# SCH_RTK2B_Micro_F9P_Breakout_Board_v2_0_.net
KiCad netlist of a schematic drawn in EasyEDA
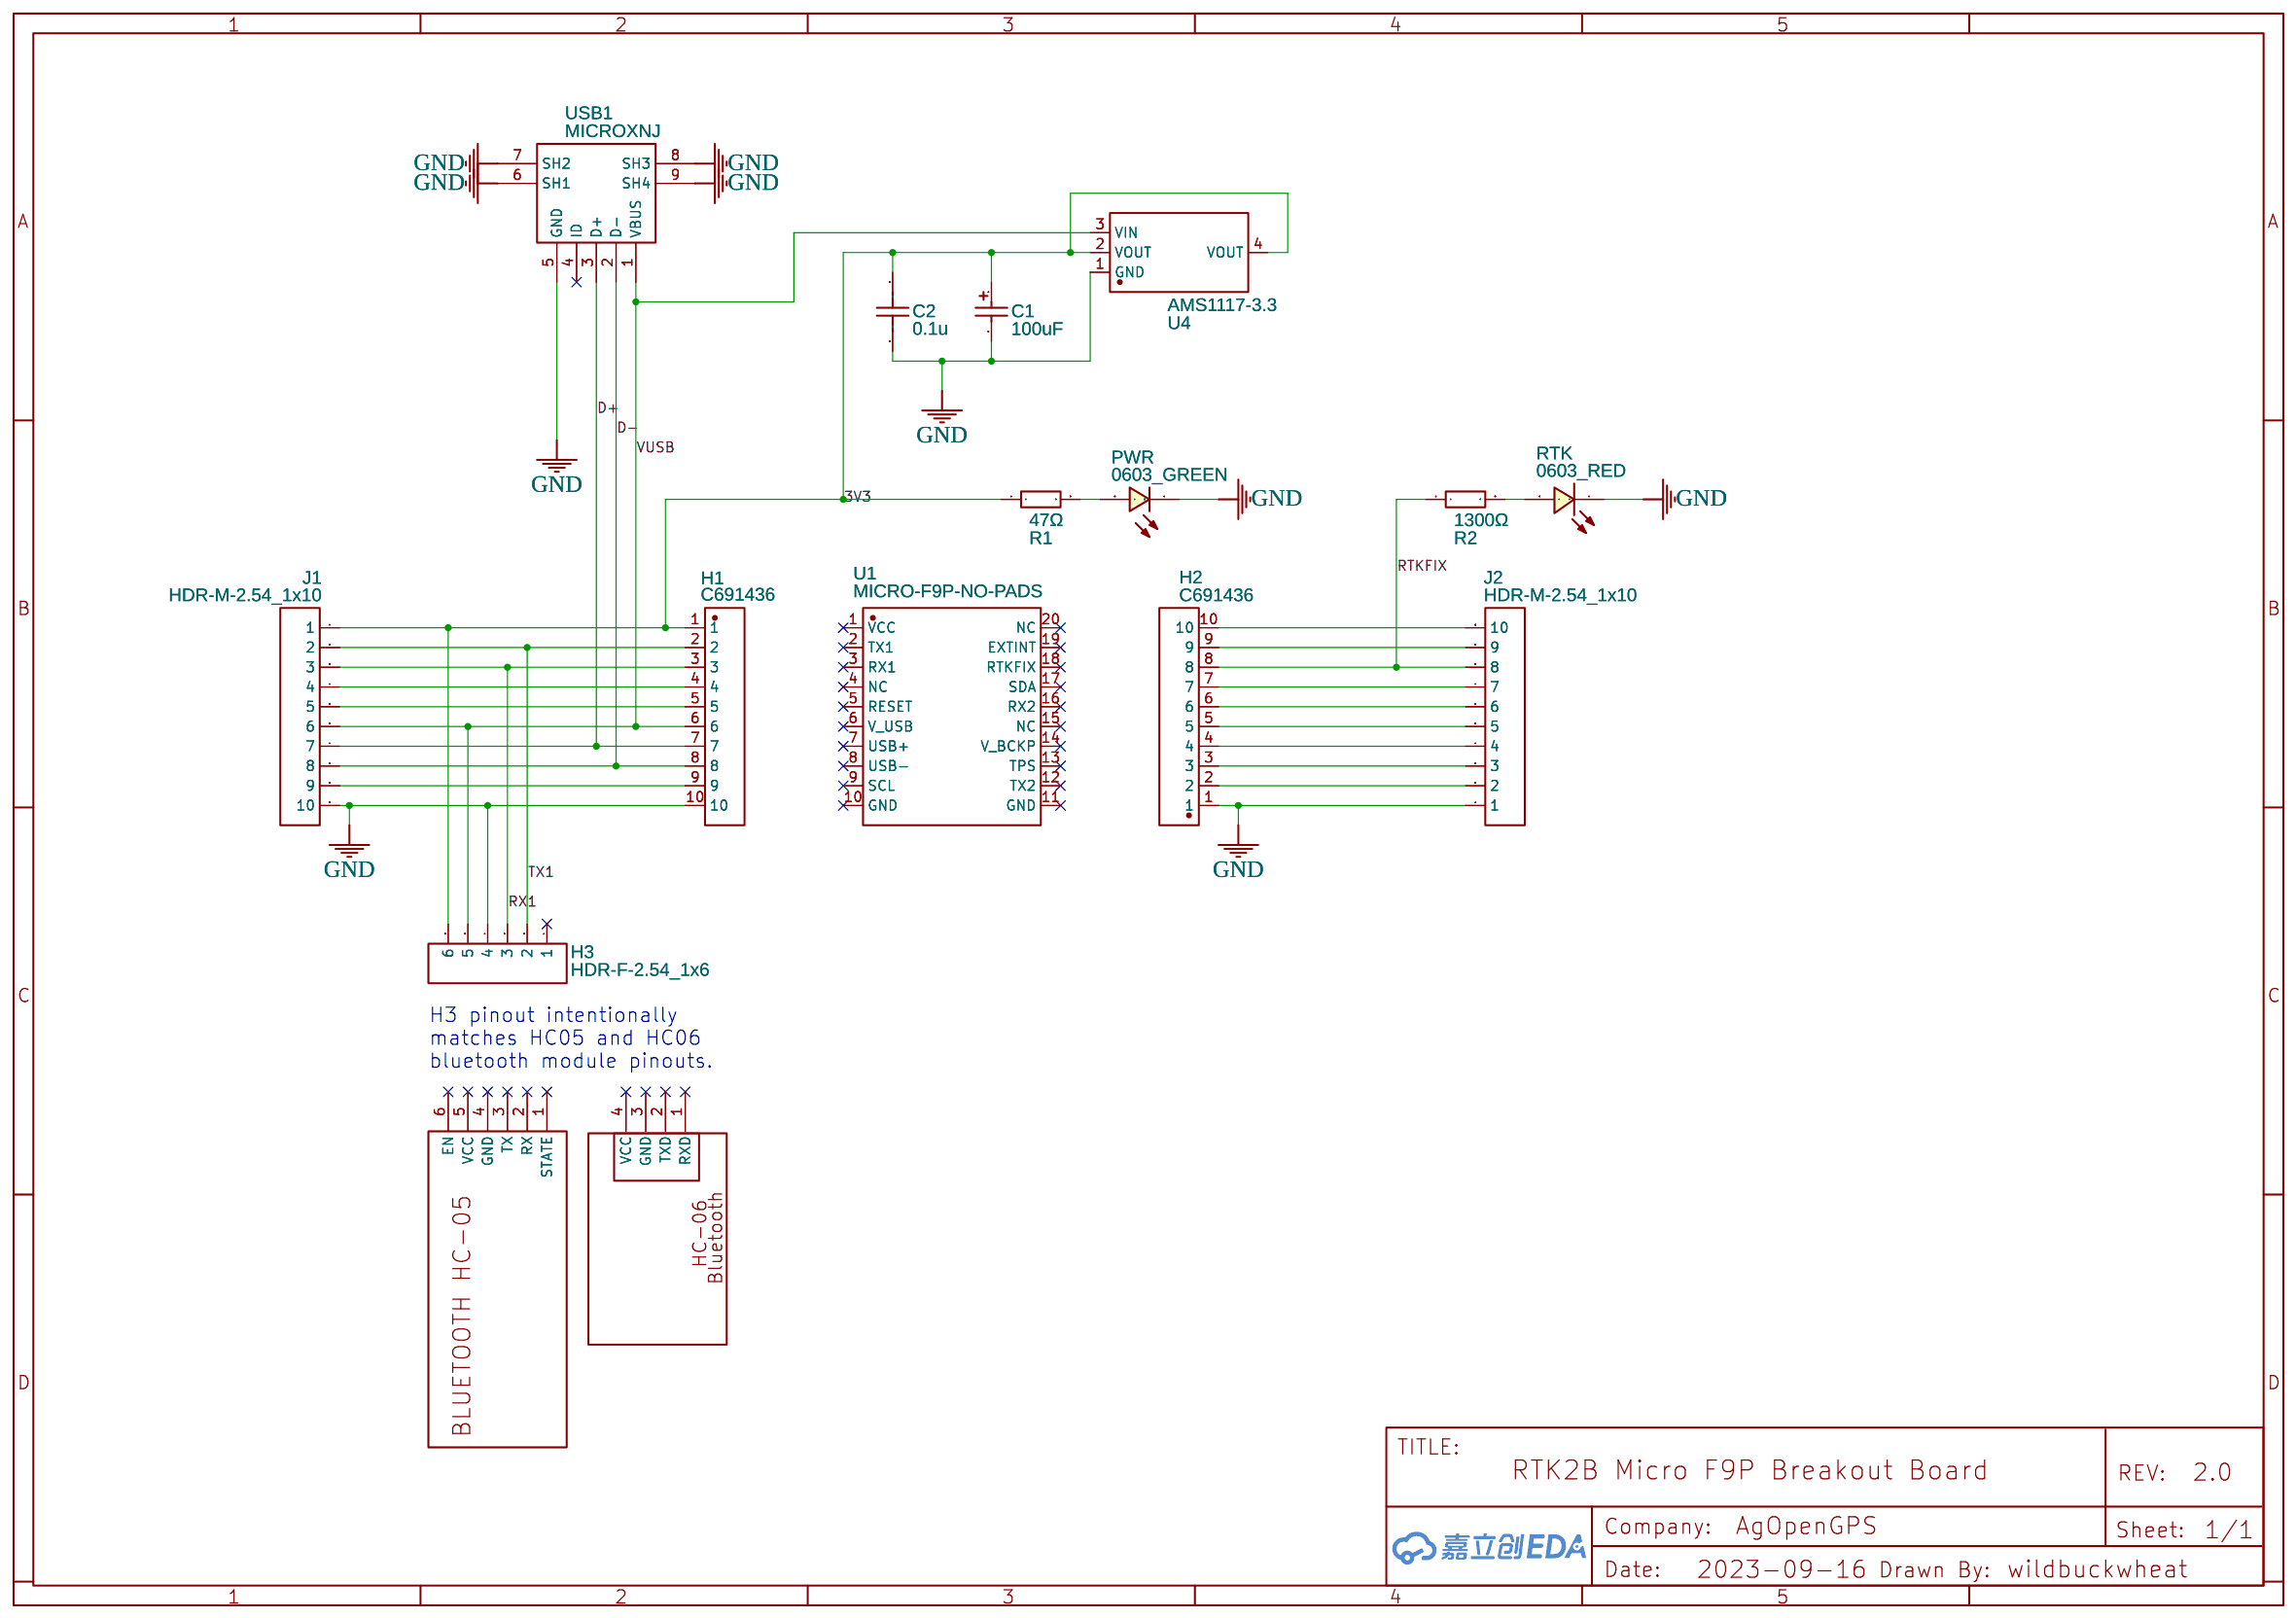
[diagram p0: schematic sheet]

(export (version "E")
  (design (tool "Eeschema 10.0.6"))
  (components
    (comp (ref "C1")
      (value "100uF")
      (fields (field (name "Manufacturer Part") "TAJB107K006RNJ") (field (name "Manufacturer") "Kyocera AVX"))
      (libsource (lib "") (part "TAJB107K006RNJ"))
    )
    (comp (ref "C2") (value "0.1u") (libsource (lib "") (part "C_0603_US")))
    (comp (ref "H1")
      (value "C691436")
      (fields (field (name "Manufacturer") "BOOMELE(Boom Precision Elec)"))
      (libsource (lib "") (part "C691436"))
    )
    (comp (ref "H2")
      (value "C691436")
      (fields (field (name "Manufacturer") "BOOMELE(Boom Precision Elec)"))
      (libsource (lib "") (part "C691436_1"))
    )
    (comp (ref "H3") (value "HDR-F-2.54_1x6") (libsource (lib "") (part "HDR-F-2.54_1x6")))
    (comp (ref "J1") (value "HDR-M-2.54_1x10") (libsource (lib "") (part "HDR-M-2.54_1x10_1")))
    (comp (ref "J2") (value "HDR-M-2.54_1x10") (libsource (lib "") (part "HDR-M-2.54_1x10")))
    (comp (ref "MK1") (value "Modulo_Bluetooth_HC-06") (libsource (lib "") (part "Modulo_Bluetooth_HC-06")))
    (comp (ref "PWR")
      (value "0603_GREEN")
      (fields
        (field (name "Manufacturer Part") "19-217/GHC-YR1S2/3T")
        (field (name "Manufacturer") "EVERLIGHT(亿光)")
      )
      (libsource (lib "") (part "19-217/GHC-YR1S2/3T-GREEN"))
    )
    (comp (ref "R1")
      (value "47Ω")
      (fields
        (field (name "Manufacturer Part") "0603WAF470JT5E")
        (field (name "Manufacturer") "UNI-ROYAL(厚声)")
      )
      (libsource (lib "") (part "0603WAF470JT5E"))
    )
    (comp (ref "R2")
      (value "1300Ω")
      (fields
        (field (name "Manufacturer Part") "0603WAF470JT5E")
        (field (name "Manufacturer") "UNI-ROYAL(厚声)")
      )
      (libsource (lib "") (part "0603WAF470JT5E"))
    )
    (comp (ref "RTK")
      (value "0603_RED")
      (fields (field (name "Manufacturer Part") "KT-0603R"))
      (libsource (lib "") (part "KT-0603R-RED"))
    )
    (comp (ref "U1") (value "MICRO-F9P-NO-PADS") (libsource (lib "") (part "MICRO-F9P-NO-PADS")))
    (comp (ref "U2")
      (value "BLUETOOTH HC05 COPY")
      (fields (field (name "Manufacturer Part") "BLUETOOTH HC05"))
      (libsource (lib "") (part "BLUETOOTH HC05 COPY"))
    )
    (comp (ref "U4")
      (value "AMS1117-3.3")
      (fields (field (name "Manufacturer") "AMS"))
      (libsource (lib "") (part "AMS1117-3.3"))
    )
    (comp (ref "USB1")
      (value "MICROXNJ")
      (fields (field (name "Manufacturer Part") "MicroXNJ") (field (name "Manufacturer") "SHOU HAN(首韩)"))
      (libsource (lib "") (part "MICROXNJ"))
    )
  )
  (nets
    (net (code "1") (name "/3V3") (class "Default")
      (node (ref "C1") (pin "1") (pinfunction "1_1") (pintype "input"))
      (node (ref "C2") (pin "2") (pinfunction "2_2") (pintype "unspecified"))
      (node (ref "H1") (pin "1") (pinfunction "1_1") (pintype "unspecified"))
      (node (ref "H3") (pin "6") (pinfunction "6_6") (pintype "input"))
      (node (ref "J1") (pin "1") (pinfunction "1_1") (pintype "unspecified"))
      (node (ref "R1") (pin "1") (pinfunction "1_1") (pintype "input"))
      (node (ref "U4") (pin "2") (pinfunction "VOUT_2") (pintype "unspecified"))
      (node (ref "U4") (pin "4") (pinfunction "VOUT_4") (pintype "unspecified"))
    )
    (net (code "2") (name "/D+") (class "Default")
      (node (ref "H1") (pin "7") (pinfunction "7_7") (pintype "unspecified"))
      (node (ref "J1") (pin "7") (pinfunction "7_7") (pintype "unspecified"))
      (node (ref "USB1") (pin "3") (pinfunction "D+_3") (pintype "unspecified"))
    )
    (net (code "3") (name "/D-") (class "Default")
      (node (ref "H1") (pin "8") (pinfunction "8_8") (pintype "unspecified"))
      (node (ref "J1") (pin "8") (pinfunction "8_8") (pintype "unspecified"))
      (node (ref "USB1") (pin "2") (pinfunction "D-_2") (pintype "unspecified"))
    )
    (net (code "4") (name "/RTKFIX") (class "Default")
      (node (ref "H2") (pin "8") (pinfunction "8_8") (pintype "unspecified"))
      (node (ref "J2") (pin "8") (pinfunction "8_8") (pintype "unspecified"))
      (node (ref "R2") (pin "1") (pinfunction "1_1") (pintype "input"))
    )
    (net (code "5") (name "/RX1") (class "Default")
      (node (ref "H1") (pin "3") (pinfunction "3_3") (pintype "unspecified"))
      (node (ref "H3") (pin "3") (pinfunction "3_3") (pintype "input"))
      (node (ref "J1") (pin "3") (pinfunction "3_3") (pintype "unspecified"))
    )
    (net (code "6") (name "/TX1") (class "Default")
      (node (ref "H1") (pin "2") (pinfunction "2_2") (pintype "unspecified"))
      (node (ref "H3") (pin "2") (pinfunction "2_2") (pintype "input"))
      (node (ref "J1") (pin "2") (pinfunction "2_2") (pintype "unspecified"))
    )
    (net (code "7") (name "/VUSB") (class "Default")
      (node (ref "H1") (pin "6") (pinfunction "6_6") (pintype "unspecified"))
      (node (ref "H3") (pin "5") (pinfunction "5_5") (pintype "input"))
      (node (ref "J1") (pin "6") (pinfunction "6_6") (pintype "unspecified"))
      (node (ref "U4") (pin "3") (pinfunction "VIN_3") (pintype "unspecified"))
      (node (ref "USB1") (pin "1") (pinfunction "VBUS_1") (pintype "unspecified"))
    )
    (net (code "8") (name "GND") (class "Default")
      (node (ref "C1") (pin "2") (pinfunction "2_2") (pintype "input"))
      (node (ref "C2") (pin "1") (pinfunction "1_1") (pintype "unspecified"))
      (node (ref "H1") (pin "10") (pinfunction "10_10") (pintype "unspecified"))
      (node (ref "H2") (pin "1") (pinfunction "1_1") (pintype "unspecified"))
      (node (ref "H3") (pin "4") (pinfunction "4_4") (pintype "input"))
      (node (ref "J1") (pin "10") (pinfunction "10_10") (pintype "unspecified"))
      (node (ref "J2") (pin "1") (pinfunction "1_1") (pintype "unspecified"))
      (node (ref "PWR") (pin "1") (pinfunction "C_1") (pintype "input"))
      (node (ref "RTK") (pin "1") (pinfunction "K_1") (pintype "unspecified"))
      (node (ref "U4") (pin "1") (pinfunction "GND_1") (pintype "unspecified"))
      (node (ref "USB1") (pin "5") (pinfunction "GND_5") (pintype "unspecified"))
      (node (ref "USB1") (pin "6") (pinfunction "SH1_6") (pintype "unspecified"))
      (node (ref "USB1") (pin "7") (pinfunction "SH2_7") (pintype "unspecified"))
      (node (ref "USB1") (pin "8") (pinfunction "SH3_8") (pintype "unspecified"))
      (node (ref "USB1") (pin "9") (pinfunction "SH4_9") (pintype "unspecified"))
    )
    (net (code "9") (name "Net-(H1-Pad4)") (class "Default")
      (node (ref "H1") (pin "4") (pinfunction "4_4") (pintype "unspecified"))
      (node (ref "J1") (pin "4") (pinfunction "4_4") (pintype "unspecified"))
    )
    (net (code "10") (name "Net-(H1-Pad5)") (class "Default")
      (node (ref "H1") (pin "5") (pinfunction "5_5") (pintype "unspecified"))
      (node (ref "J1") (pin "5") (pinfunction "5_5") (pintype "unspecified"))
    )
    (net (code "11") (name "Net-(H1-Pad9)") (class "Default")
      (node (ref "H1") (pin "9") (pinfunction "9_9") (pintype "unspecified"))
      (node (ref "J1") (pin "9") (pinfunction "9_9") (pintype "unspecified"))
    )
    (net (code "12") (name "Net-(H2-Pad2)") (class "Default")
      (node (ref "H2") (pin "2") (pinfunction "2_2") (pintype "unspecified"))
      (node (ref "J2") (pin "2") (pinfunction "2_2") (pintype "unspecified"))
    )
    (net (code "13") (name "Net-(H2-Pad3)") (class "Default")
      (node (ref "H2") (pin "3") (pinfunction "3_3") (pintype "unspecified"))
      (node (ref "J2") (pin "3") (pinfunction "3_3") (pintype "unspecified"))
    )
    (net (code "14") (name "Net-(H2-Pad4)") (class "Default")
      (node (ref "H2") (pin "4") (pinfunction "4_4") (pintype "unspecified"))
      (node (ref "J2") (pin "4") (pinfunction "4_4") (pintype "unspecified"))
    )
    (net (code "15") (name "Net-(H2-Pad5)") (class "Default")
      (node (ref "H2") (pin "5") (pinfunction "5_5") (pintype "unspecified"))
      (node (ref "J2") (pin "5") (pinfunction "5_5") (pintype "unspecified"))
    )
    (net (code "16") (name "Net-(H2-Pad6)") (class "Default")
      (node (ref "H2") (pin "6") (pinfunction "6_6") (pintype "unspecified"))
      (node (ref "J2") (pin "6") (pinfunction "6_6") (pintype "unspecified"))
    )
    (net (code "17") (name "Net-(H2-Pad7)") (class "Default")
      (node (ref "H2") (pin "7") (pinfunction "7_7") (pintype "unspecified"))
      (node (ref "J2") (pin "7") (pinfunction "7_7") (pintype "unspecified"))
    )
    (net (code "18") (name "Net-(H2-Pad9)") (class "Default")
      (node (ref "H2") (pin "9") (pinfunction "9_9") (pintype "unspecified"))
      (node (ref "J2") (pin "9") (pinfunction "9_9") (pintype "unspecified"))
    )
    (net (code "19") (name "Net-(H2-Pad10)") (class "Default")
      (node (ref "H2") (pin "10") (pinfunction "10_10") (pintype "unspecified"))
      (node (ref "J2") (pin "10") (pinfunction "10_10") (pintype "unspecified"))
    )
    (net (code "20") (name "Net-(PWR-A)") (class "Default")
      (node (ref "PWR") (pin "2") (pinfunction "A_2") (pintype "input"))
      (node (ref "R1") (pin "2") (pinfunction "2_2") (pintype "input"))
    )
    (net (code "21") (name "Net-(RTK-A)") (class "Default")
      (node (ref "R2") (pin "2") (pinfunction "2_2") (pintype "input"))
      (node (ref "RTK") (pin "2") (pinfunction "A_2") (pintype "unspecified"))
    )
    (net (code "22") (name "unconnected-(H3-Pad1)") (class "Default")
      (node (ref "H3") (pin "1") (pinfunction "1_1") (pintype "input+no_connect"))
    )
    (net (code "23") (name "unconnected-(MK1-GND-Pad3)") (class "Default")
      (node (ref "MK1") (pin "3") (pinfunction "GND_3") (pintype "unspecified+no_connect"))
    )
    (net (code "24") (name "unconnected-(MK1-RXD-Pad1)") (class "Default")
      (node (ref "MK1") (pin "1") (pinfunction "RXD_1") (pintype "unspecified+no_connect"))
    )
    (net (code "25") (name "unconnected-(MK1-TXD-Pad2)") (class "Default")
      (node (ref "MK1") (pin "2") (pinfunction "TXD_2") (pintype "unspecified+no_connect"))
    )
    (net (code "26") (name "unconnected-(MK1-VCC-Pad4)") (class "Default")
      (node (ref "MK1") (pin "4") (pinfunction "VCC_4") (pintype "unspecified+no_connect"))
    )
    (net (code "27") (name "unconnected-(U1-EXTINT-Pad19)") (class "Default")
      (node (ref "U1") (pin "19") (pinfunction "EXTINT_19") (pintype "unspecified+no_connect"))
    )
    (net (code "28") (name "unconnected-(U1-GND-Pad10)") (class "Default")
      (node (ref "U1") (pin "10") (pinfunction "GND_10") (pintype "unspecified+no_connect"))
    )
    (net (code "29") (name "unconnected-(U1-GND-Pad11)") (class "Default")
      (node (ref "U1") (pin "11") (pinfunction "GND_11") (pintype "unspecified+no_connect"))
    )
    (net (code "30") (name "unconnected-(U1-NC-Pad4)") (class "Default")
      (node (ref "U1") (pin "4") (pinfunction "NC_4") (pintype "unspecified+no_connect"))
    )
    (net (code "31") (name "unconnected-(U1-NC-Pad15)") (class "Default")
      (node (ref "U1") (pin "15") (pinfunction "NC_15") (pintype "unspecified+no_connect"))
    )
    (net (code "32") (name "unconnected-(U1-NC-Pad20)") (class "Default")
      (node (ref "U1") (pin "20") (pinfunction "NC_20") (pintype "unspecified+no_connect"))
    )
    (net (code "33") (name "unconnected-(U1-RESET-Pad5)") (class "Default")
      (node (ref "U1") (pin "5") (pinfunction "RESET_5") (pintype "unspecified+no_connect"))
    )
    (net (code "34") (name "unconnected-(U1-RTKFIX-Pad18)") (class "Default")
      (node (ref "U1") (pin "18") (pinfunction "RTKFIX_18") (pintype "unspecified+no_connect"))
    )
    (net (code "35") (name "unconnected-(U1-RX1-Pad3)") (class "Default")
      (node (ref "U1") (pin "3") (pinfunction "RX1_3") (pintype "unspecified+no_connect"))
    )
    (net (code "36") (name "unconnected-(U1-RX2-Pad16)") (class "Default")
      (node (ref "U1") (pin "16") (pinfunction "RX2_16") (pintype "unspecified+no_connect"))
    )
    (net (code "37") (name "unconnected-(U1-SCL-Pad9)") (class "Default")
      (node (ref "U1") (pin "9") (pinfunction "SCL_9") (pintype "unspecified+no_connect"))
    )
    (net (code "38") (name "unconnected-(U1-SDA-Pad17)") (class "Default")
      (node (ref "U1") (pin "17") (pinfunction "SDA_17") (pintype "unspecified+no_connect"))
    )
    (net (code "39") (name "unconnected-(U1-TPS-Pad13)") (class "Default")
      (node (ref "U1") (pin "13") (pinfunction "TPS_13") (pintype "unspecified+no_connect"))
    )
    (net (code "40") (name "unconnected-(U1-TX1-Pad2)") (class "Default")
      (node (ref "U1") (pin "2") (pinfunction "TX1_2") (pintype "unspecified+no_connect"))
    )
    (net (code "41") (name "unconnected-(U1-TX2-Pad12)") (class "Default")
      (node (ref "U1") (pin "12") (pinfunction "TX2_12") (pintype "unspecified+no_connect"))
    )
    (net (code "42") (name "unconnected-(U1-USB+-Pad7)") (class "Default")
      (node (ref "U1") (pin "7") (pinfunction "USB+_7") (pintype "unspecified+no_connect"))
    )
    (net (code "43") (name "unconnected-(U1-USB--Pad8)") (class "Default")
      (node (ref "U1") (pin "8") (pinfunction "USB-_8") (pintype "unspecified+no_connect"))
    )
    (net (code "44") (name "unconnected-(U1-VCC-Pad1)") (class "Default")
      (node (ref "U1") (pin "1") (pinfunction "VCC_1") (pintype "unspecified+no_connect"))
    )
    (net (code "45") (name "unconnected-(U1-V_BCKP-Pad14)") (class "Default")
      (node (ref "U1") (pin "14") (pinfunction "V_BCKP_14") (pintype "unspecified+no_connect"))
    )
    (net (code "46") (name "unconnected-(U1-V_USB-Pad6)") (class "Default")
      (node (ref "U1") (pin "6") (pinfunction "V_USB_6") (pintype "unspecified+no_connect"))
    )
    (net (code "47") (name "unconnected-(U2-EN-Pad6)") (class "Default")
      (node (ref "U2") (pin "6") (pinfunction "EN_6") (pintype "unspecified+no_connect"))
    )
    (net (code "48") (name "unconnected-(U2-GND-Pad4)") (class "Default")
      (node (ref "U2") (pin "4") (pinfunction "GND_4") (pintype "unspecified+no_connect"))
    )
    (net (code "49") (name "unconnected-(U2-RX-Pad2)") (class "Default")
      (node (ref "U2") (pin "2") (pinfunction "RX_2") (pintype "unspecified+no_connect"))
    )
    (net (code "50") (name "unconnected-(U2-STATE-Pad1)") (class "Default")
      (node (ref "U2") (pin "1") (pinfunction "STATE_1") (pintype "unspecified+no_connect"))
    )
    (net (code "51") (name "unconnected-(U2-TX-Pad3)") (class "Default")
      (node (ref "U2") (pin "3") (pinfunction "TX_3") (pintype "unspecified+no_connect"))
    )
    (net (code "52") (name "unconnected-(U2-VCC-Pad5)") (class "Default")
      (node (ref "U2") (pin "5") (pinfunction "VCC_5") (pintype "unspecified+no_connect"))
    )
    (net (code "53") (name "unconnected-(USB1-ID-Pad4)") (class "Default")
      (node (ref "USB1") (pin "4") (pinfunction "ID_4") (pintype "unspecified+no_connect"))
    )
  )
)
